# Switch_sheet.net
KiCad netlist of a schematic drawn in Altium Designer
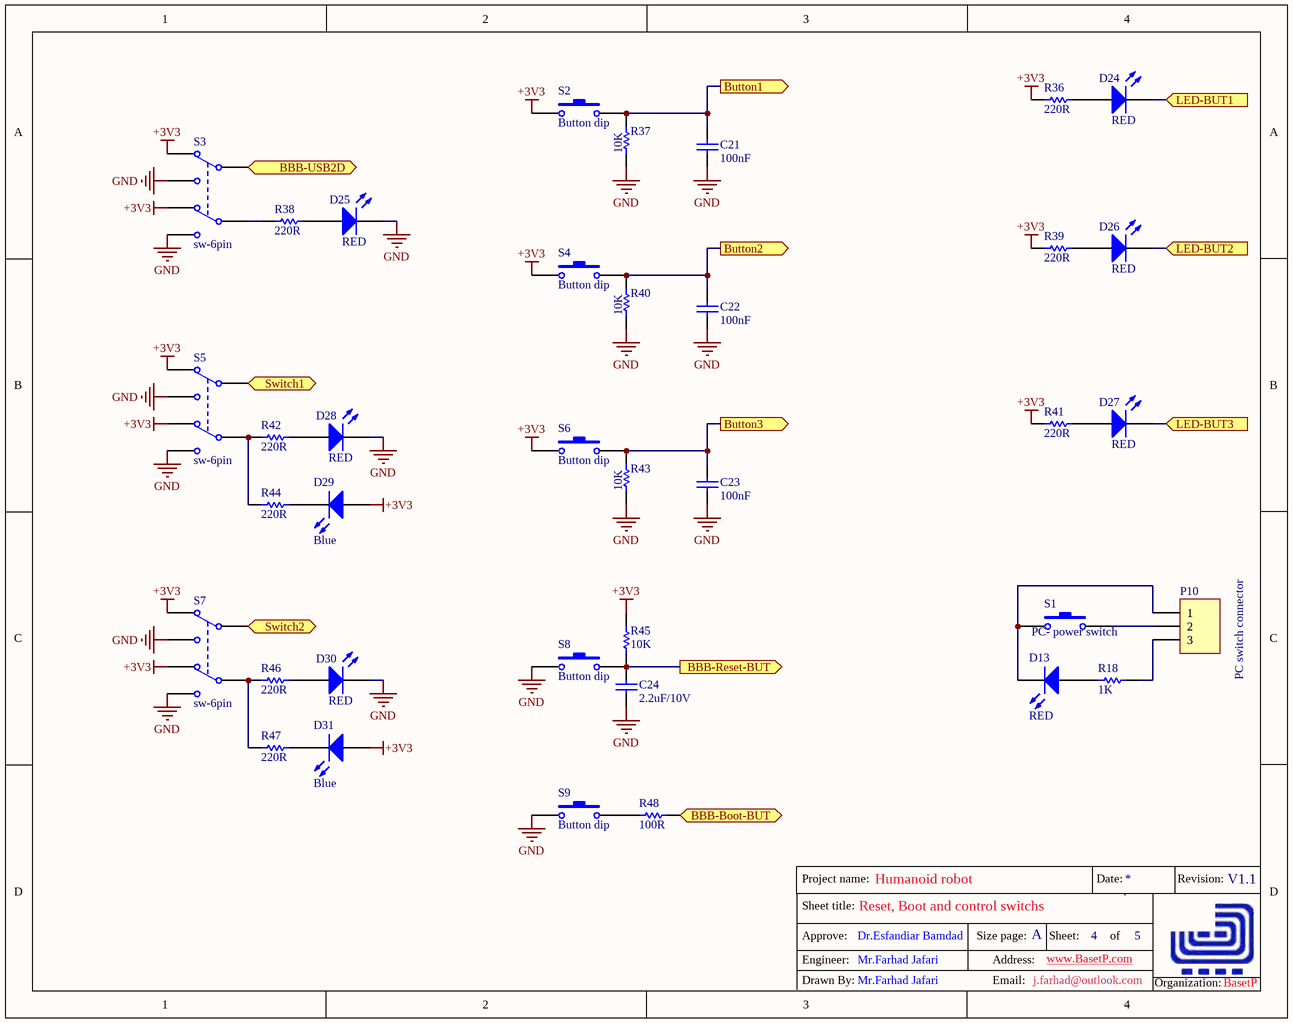
[diagram p0: Switch sheet.SchDoc]

(export (version "E")
  (design (tool "Eeschema 10.0.6"))
  (components
    (comp (ref "C21")
      (value "100nF")
      (footprint "0805")
      (description "Ceramic Chip Capacitor - Standard")
      (fields (field (name "Comment") "C0805") (field (name "PUBLISHER") "Altium Limited"))
      (libsource (lib "KEMET Chip Capacitor") (part "C0805"))
    )
    (comp (ref "C22")
      (value "100nF")
      (footprint "0805")
      (description "Ceramic Chip Capacitor - Standard")
      (fields (field (name "Comment") "C0805") (field (name "PUBLISHER") "Altium Limited"))
      (libsource (lib "KEMET Chip Capacitor") (part "C0805"))
    )
    (comp (ref "C23")
      (value "100nF")
      (footprint "0805")
      (description "Ceramic Chip Capacitor - Standard")
      (fields (field (name "Comment") "C0805") (field (name "PUBLISHER") "Altium Limited"))
      (libsource (lib "KEMET Chip Capacitor") (part "C0805"))
    )
    (comp (ref "C24")
      (value "2.2uF/10V")
      (footprint "0805")
      (description "Ceramic Chip Capacitor - Standard")
      (fields (field (name "Comment") "C0805") (field (name "PUBLISHER") "Altium Limited"))
      (libsource (lib "KEMET Chip Capacitor") (part "C0805"))
    )
    (comp (ref "D13")
      (value "RED")
      (footprint "LED Red-0805")
      (description "High Performance Chip LED, Amber")
      (fields (field (name "PUBLISHER") "Altium Limited"))
      (libsource (lib "Farhad_Library") (part "LED-RED"))
    )
    (comp (ref "D24")
      (value "RED")
      (footprint "LED Red-0805")
      (description "High Performance Chip LED, Amber")
      (fields (field (name "PUBLISHER") "Altium Limited"))
      (libsource (lib "Farhad_Library") (part "LED-RED"))
    )
    (comp (ref "D25")
      (value "RED")
      (footprint "LED Red-0805")
      (description "High Performance Chip LED, Amber")
      (fields (field (name "PUBLISHER") "Altium Limited"))
      (libsource (lib "Farhad_Library") (part "LED-RED"))
    )
    (comp (ref "D26")
      (value "RED")
      (footprint "LED Red-0805")
      (description "High Performance Chip LED, Amber")
      (fields (field (name "PUBLISHER") "Altium Limited"))
      (libsource (lib "Farhad_Library") (part "LED-RED"))
    )
    (comp (ref "D27")
      (value "RED")
      (footprint "LED Red-0805")
      (description "High Performance Chip LED, Amber")
      (fields (field (name "PUBLISHER") "Altium Limited"))
      (libsource (lib "Farhad_Library") (part "LED-RED"))
    )
    (comp (ref "D28")
      (value "RED")
      (footprint "LED Red-0805")
      (description "High Performance Chip LED, Amber")
      (fields (field (name "PUBLISHER") "Altium Limited"))
      (libsource (lib "Farhad_Library") (part "LED-RED"))
    )
    (comp (ref "D29")
      (value "Blue")
      (footprint "led Blue-0805")
      (description "High Performance Chip LED, Amber")
      (fields (field (name "PUBLISHER") "Altium Limited"))
      (libsource (lib "Farhad_Library") (part "LED-BLUE"))
    )
    (comp (ref "D30")
      (value "RED")
      (footprint "LED Red-0805")
      (description "High Performance Chip LED, Amber")
      (fields (field (name "PUBLISHER") "Altium Limited"))
      (libsource (lib "Farhad_Library") (part "LED-RED"))
    )
    (comp (ref "D31")
      (value "Blue")
      (footprint "led Blue-0805")
      (description "High Performance Chip LED, Amber")
      (fields (field (name "PUBLISHER") "Altium Limited"))
      (libsource (lib "Farhad_Library") (part "LED-BLUE"))
    )
    (comp (ref "P10")
      (value "PC switch connector")
      (footprint "HDR1X3")
      (description "Header, 3-Pin")
      (fields (field (name "PUBLISHER") "Altium Limited"))
      (libsource (lib "Farhad_Library") (part "Header 3"))
    )
    (comp (ref "R18")
      (value "1K")
      (footprint "6-0805")
      (fields (field (name "PUBLISHER") "Altium Limited"))
      (libsource (lib "Panasonic Resistor") (part "ERJ6RS"))
    )
    (comp (ref "R36")
      (value "220R")
      (footprint "6-0805")
      (fields (field (name "PUBLISHER") "Altium Limited"))
      (libsource (lib "Panasonic Resistor") (part "ERJ6RS"))
    )
    (comp (ref "R37")
      (value "10K")
      (footprint "6-0805")
      (fields (field (name "PUBLISHER") "Altium Limited"))
      (libsource (lib "Panasonic Resistor") (part "ERJ6RS"))
    )
    (comp (ref "R38")
      (value "220R")
      (footprint "6-0805")
      (fields (field (name "PUBLISHER") "Altium Limited"))
      (libsource (lib "Panasonic Resistor") (part "ERJ6RS"))
    )
    (comp (ref "R39")
      (value "220R")
      (footprint "6-0805")
      (fields (field (name "PUBLISHER") "Altium Limited"))
      (libsource (lib "Panasonic Resistor") (part "ERJ6RS"))
    )
    (comp (ref "R40")
      (value "10K")
      (footprint "6-0805")
      (fields (field (name "PUBLISHER") "Altium Limited"))
      (libsource (lib "Panasonic Resistor") (part "ERJ6RS"))
    )
    (comp (ref "R41")
      (value "220R")
      (footprint "6-0805")
      (fields (field (name "PUBLISHER") "Altium Limited"))
      (libsource (lib "Panasonic Resistor") (part "ERJ6RS"))
    )
    (comp (ref "R42")
      (value "220R")
      (footprint "6-0805")
      (fields (field (name "PUBLISHER") "Altium Limited"))
      (libsource (lib "Panasonic Resistor") (part "ERJ6RS"))
    )
    (comp (ref "R43")
      (value "10K")
      (footprint "6-0805")
      (fields (field (name "PUBLISHER") "Altium Limited"))
      (libsource (lib "Panasonic Resistor") (part "ERJ6RS"))
    )
    (comp (ref "R44")
      (value "220R")
      (footprint "6-0805")
      (fields (field (name "PUBLISHER") "Altium Limited"))
      (libsource (lib "Panasonic Resistor") (part "ERJ6RS"))
    )
    (comp (ref "R45")
      (value "10K")
      (footprint "6-0805")
      (fields (field (name "PUBLISHER") "Altium Limited"))
      (libsource (lib "Panasonic Resistor") (part "ERJ6RS"))
    )
    (comp (ref "R46")
      (value "220R")
      (footprint "6-0805")
      (fields (field (name "PUBLISHER") "Altium Limited"))
      (libsource (lib "Panasonic Resistor") (part "ERJ6RS"))
    )
    (comp (ref "R47")
      (value "220R")
      (footprint "6-0805")
      (fields (field (name "PUBLISHER") "Altium Limited"))
      (libsource (lib "Panasonic Resistor") (part "ERJ6RS"))
    )
    (comp (ref "R48")
      (value "100R")
      (footprint "6-0805")
      (fields (field (name "PUBLISHER") "Altium Limited"))
      (libsource (lib "Panasonic Resistor") (part "ERJ6RS"))
    )
    (comp (ref "S1")
      (value "PC- power switch")
      (footprint "DTS-6x")
      (description "Switch")
      (libsource (lib "Farhad_Library") (part "Button dip"))
    )
    (comp (ref "S2")
      (value "Button dip")
      (footprint "DTS-6x")
      (description "Switch")
      (libsource (lib "Farhad_Library") (part "Button dip"))
    )
    (comp (ref "S3")
      (value "sw-6pin")
      (footprint "sw-6pin")
      (libsource (lib "Farhad_Library") (part "sw-6pin"))
    )
    (comp (ref "S4")
      (value "Button dip")
      (footprint "DTS-6x")
      (description "Switch")
      (libsource (lib "Farhad_Library") (part "Button dip"))
    )
    (comp (ref "S5")
      (value "sw-6pin")
      (footprint "sw-6pin")
      (libsource (lib "Farhad_Library") (part "sw-6pin"))
    )
    (comp (ref "S6")
      (value "Button dip")
      (footprint "DTS-6x")
      (description "Switch")
      (libsource (lib "Farhad_Library") (part "Button dip"))
    )
    (comp (ref "S7")
      (value "sw-6pin")
      (footprint "sw-6pin")
      (libsource (lib "Farhad_Library") (part "sw-6pin"))
    )
    (comp (ref "S8")
      (value "Button dip")
      (footprint "DTS-6x")
      (description "Switch")
      (libsource (lib "Farhad_Library") (part "Button dip"))
    )
    (comp (ref "S9")
      (value "Button dip")
      (footprint "DTS-6x")
      (description "Switch")
      (libsource (lib "Farhad_Library") (part "Button dip"))
    )
  )
  (nets
    (net (code "1") (name "+3V3") (class "Default")
      (node (ref "D29") (pin "1") (pinfunction "A_1") (pintype "passive"))
      (node (ref "D31") (pin "1") (pinfunction "A_1") (pintype "passive"))
      (node (ref "R36") (pin "1") (pinfunction "1_1") (pintype "passive"))
      (node (ref "R39") (pin "1") (pinfunction "1_1") (pintype "passive"))
      (node (ref "R41") (pin "1") (pinfunction "1_1") (pintype "passive"))
      (node (ref "R45") (pin "2") (pinfunction "2_2") (pintype "passive"))
      (node (ref "S2") (pin "1") (pinfunction "1_1") (pintype "passive"))
      (node (ref "S3") (pin "1") (pinfunction "NC1_1") (pintype "passive"))
      (node (ref "S3") (pin "6") (pinfunction "NC2_6") (pintype "passive"))
      (node (ref "S4") (pin "1") (pinfunction "1_1") (pintype "passive"))
      (node (ref "S5") (pin "1") (pinfunction "NC1_1") (pintype "passive"))
      (node (ref "S5") (pin "6") (pinfunction "NC2_6") (pintype "passive"))
      (node (ref "S6") (pin "1") (pinfunction "1_1") (pintype "passive"))
      (node (ref "S7") (pin "1") (pinfunction "NC1_1") (pintype "passive"))
      (node (ref "S7") (pin "6") (pinfunction "NC2_6") (pintype "passive"))
    )
    (net (code "2") (name "/BBB-Boot-BUT") (class "Default")
      (node (ref "R48") (pin "1") (pinfunction "1_1") (pintype "passive"))
    )
    (net (code "3") (name "/BBB-Reset-BUT") (class "Default")
      (node (ref "C24") (pin "2") (pinfunction "2_2") (pintype "passive"))
      (node (ref "R45") (pin "1") (pinfunction "1_1") (pintype "passive"))
      (node (ref "S8") (pin "2") (pinfunction "2_2") (pintype "passive"))
    )
    (net (code "4") (name "/BBB-USB2D") (class "Default")
      (node (ref "S3") (pin "2") (pinfunction "COMMON1_2") (pintype "passive"))
    )
    (net (code "5") (name "/Button1") (class "Default")
      (node (ref "C21") (pin "2") (pinfunction "2_2") (pintype "passive"))
      (node (ref "R37") (pin "2") (pinfunction "2_2") (pintype "passive"))
      (node (ref "S2") (pin "2") (pinfunction "2_2") (pintype "passive"))
    )
    (net (code "6") (name "/Button2") (class "Default")
      (node (ref "C22") (pin "2") (pinfunction "2_2") (pintype "passive"))
      (node (ref "R40") (pin "2") (pinfunction "2_2") (pintype "passive"))
      (node (ref "S4") (pin "2") (pinfunction "2_2") (pintype "passive"))
    )
    (net (code "7") (name "/Button3") (class "Default")
      (node (ref "C23") (pin "2") (pinfunction "2_2") (pintype "passive"))
      (node (ref "R43") (pin "2") (pinfunction "2_2") (pintype "passive"))
      (node (ref "S6") (pin "2") (pinfunction "2_2") (pintype "passive"))
    )
    (net (code "8") (name "/LED-BUT1") (class "Default")
      (node (ref "D24") (pin "2") (pinfunction "K_2") (pintype "passive"))
    )
    (net (code "9") (name "/LED-BUT2") (class "Default")
      (node (ref "D26") (pin "2") (pinfunction "K_2") (pintype "passive"))
    )
    (net (code "10") (name "/LED-BUT3") (class "Default")
      (node (ref "D27") (pin "2") (pinfunction "K_2") (pintype "passive"))
    )
    (net (code "11") (name "/Switch1") (class "Default")
      (node (ref "S5") (pin "2") (pinfunction "COMMON1_2") (pintype "passive"))
    )
    (net (code "12") (name "/Switch2") (class "Default")
      (node (ref "S7") (pin "2") (pinfunction "COMMON1_2") (pintype "passive"))
    )
    (net (code "13") (name "GND") (class "Default")
      (node (ref "C21") (pin "1") (pinfunction "1_1") (pintype "passive"))
      (node (ref "C22") (pin "1") (pinfunction "1_1") (pintype "passive"))
      (node (ref "C23") (pin "1") (pinfunction "1_1") (pintype "passive"))
      (node (ref "C24") (pin "1") (pinfunction "1_1") (pintype "passive"))
      (node (ref "D25") (pin "2") (pinfunction "K_2") (pintype "passive"))
      (node (ref "D28") (pin "2") (pinfunction "K_2") (pintype "passive"))
      (node (ref "D30") (pin "2") (pinfunction "K_2") (pintype "passive"))
      (node (ref "R37") (pin "1") (pinfunction "1_1") (pintype "passive"))
      (node (ref "R40") (pin "1") (pinfunction "1_1") (pintype "passive"))
      (node (ref "R43") (pin "1") (pinfunction "1_1") (pintype "passive"))
      (node (ref "S3") (pin "3") (pinfunction "NO1_3") (pintype "passive"))
      (node (ref "S3") (pin "4") (pinfunction "NO2_4") (pintype "passive"))
      (node (ref "S5") (pin "3") (pinfunction "NO1_3") (pintype "passive"))
      (node (ref "S5") (pin "4") (pinfunction "NO2_4") (pintype "passive"))
      (node (ref "S7") (pin "3") (pinfunction "NO1_3") (pintype "passive"))
      (node (ref "S7") (pin "4") (pinfunction "NO2_4") (pintype "passive"))
      (node (ref "S8") (pin "1") (pinfunction "1_1") (pintype "passive"))
      (node (ref "S9") (pin "1") (pinfunction "1_1") (pintype "passive"))
    )
    (net (code "14") (name "Net-(D13-A)") (class "Default")
      (node (ref "D13") (pin "1") (pinfunction "A_1") (pintype "passive"))
      (node (ref "R18") (pin "2") (pinfunction "2_2") (pintype "passive"))
    )
    (net (code "15") (name "Net-(D13-K)") (class "Default")
      (node (ref "D13") (pin "2") (pinfunction "K_2") (pintype "passive"))
      (node (ref "P10") (pin "1") (pinfunction "1_1") (pintype "passive"))
      (node (ref "S1") (pin "1") (pinfunction "1_1") (pintype "passive"))
    )
    (net (code "16") (name "Net-(D24-A)") (class "Default")
      (node (ref "D24") (pin "1") (pinfunction "A_1") (pintype "passive"))
      (node (ref "R36") (pin "2") (pinfunction "2_2") (pintype "passive"))
    )
    (net (code "17") (name "Net-(D25-A)") (class "Default")
      (node (ref "D25") (pin "1") (pinfunction "A_1") (pintype "passive"))
      (node (ref "R38") (pin "2") (pinfunction "2_2") (pintype "passive"))
    )
    (net (code "18") (name "Net-(D26-A)") (class "Default")
      (node (ref "D26") (pin "1") (pinfunction "A_1") (pintype "passive"))
      (node (ref "R39") (pin "2") (pinfunction "2_2") (pintype "passive"))
    )
    (net (code "19") (name "Net-(D27-A)") (class "Default")
      (node (ref "D27") (pin "1") (pinfunction "A_1") (pintype "passive"))
      (node (ref "R41") (pin "2") (pinfunction "2_2") (pintype "passive"))
    )
    (net (code "20") (name "Net-(D28-A)") (class "Default")
      (node (ref "D28") (pin "1") (pinfunction "A_1") (pintype "passive"))
      (node (ref "R42") (pin "2") (pinfunction "2_2") (pintype "passive"))
    )
    (net (code "21") (name "Net-(D29-K)") (class "Default")
      (node (ref "D29") (pin "2") (pinfunction "K_2") (pintype "passive"))
      (node (ref "R44") (pin "2") (pinfunction "2_2") (pintype "passive"))
    )
    (net (code "22") (name "Net-(D30-A)") (class "Default")
      (node (ref "D30") (pin "1") (pinfunction "A_1") (pintype "passive"))
      (node (ref "R46") (pin "2") (pinfunction "2_2") (pintype "passive"))
    )
    (net (code "23") (name "Net-(D31-K)") (class "Default")
      (node (ref "D31") (pin "2") (pinfunction "K_2") (pintype "passive"))
      (node (ref "R47") (pin "2") (pinfunction "2_2") (pintype "passive"))
    )
    (net (code "24") (name "Net-(P10-Pad2)") (class "Default")
      (node (ref "P10") (pin "2") (pinfunction "2_2") (pintype "passive"))
      (node (ref "S1") (pin "2") (pinfunction "2_2") (pintype "passive"))
    )
    (net (code "25") (name "Net-(P10-Pad3)") (class "Default")
      (node (ref "P10") (pin "3") (pinfunction "3_3") (pintype "passive"))
      (node (ref "R18") (pin "1") (pinfunction "1_1") (pintype "passive"))
    )
    (net (code "26") (name "Net-(R48-Pad2)") (class "Default")
      (node (ref "R48") (pin "2") (pinfunction "2_2") (pintype "passive"))
      (node (ref "S9") (pin "2") (pinfunction "2_2") (pintype "passive"))
    )
    (net (code "27") (name "Net-(S3-COMMON2)") (class "Default")
      (node (ref "R38") (pin "1") (pinfunction "1_1") (pintype "passive"))
      (node (ref "S3") (pin "5") (pinfunction "COMMON2_5") (pintype "passive"))
    )
    (net (code "28") (name "Net-(S5-COMMON2)") (class "Default")
      (node (ref "R42") (pin "1") (pinfunction "1_1") (pintype "passive"))
      (node (ref "R44") (pin "1") (pinfunction "1_1") (pintype "passive"))
      (node (ref "S5") (pin "5") (pinfunction "COMMON2_5") (pintype "passive"))
    )
    (net (code "29") (name "Net-(S7-COMMON2)") (class "Default")
      (node (ref "R46") (pin "1") (pinfunction "1_1") (pintype "passive"))
      (node (ref "R47") (pin "1") (pinfunction "1_1") (pintype "passive"))
      (node (ref "S7") (pin "5") (pinfunction "COMMON2_5") (pintype "passive"))
    )
  )
)
